# Sheet2.net
KiCad netlist of a schematic drawn in Altium Designer
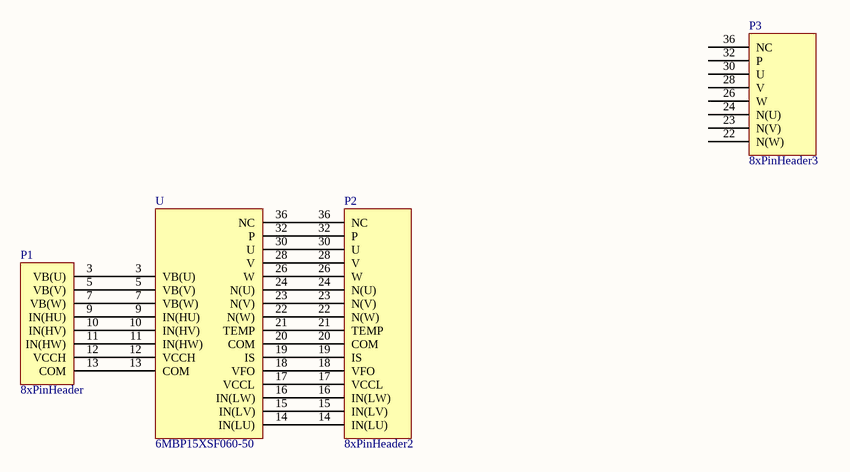
[diagram p0: Sheet2.SchDoc]

(export (version "E")
  (design (tool "Eeschema 10.0.6"))
  (components
    (comp (ref "P1")
      (value "8xPinHeader")
      (footprint "8xPinHeader")
      (libsource (lib "Schlib1") (part "8xPinHeader"))
    )
    (comp (ref "P2")
      (value "8xPinHeader2")
      (footprint "8xPinHeader2")
      (libsource (lib "Schlib1") (part "8xPinHeader2"))
    )
    (comp (ref "P3")
      (value "8xPinHeader3")
      (footprint "8xPinHeader3")
      (libsource (lib "Schlib1") (part "8xPinHeader3"))
    )
    (comp (ref "U")
      (value "6MBP15XSF060-50")
      (footprint "6MBP15XSF060-50")
      (description "600v 15a")
      (libsource (lib "Schlib1") (part "6MBP15XSF060-50"))
    )
  )
  (nets
    (net (code "1") (name "Net-(P1-COM)") (class "Default")
      (node (ref "P1") (pin "13") (pinfunction "COM_13") (pintype "passive"))
      (node (ref "U") (pin "13") (pinfunction "COM_13") (pintype "passive"))
    )
    (net (code "2") (name "Net-(P1-IN(HU))") (class "Default")
      (node (ref "P1") (pin "9") (pinfunction "IN(HU)_9") (pintype "passive"))
      (node (ref "U") (pin "9") (pinfunction "IN(HU)_9") (pintype "passive"))
    )
    (net (code "3") (name "Net-(P1-IN(HV))") (class "Default")
      (node (ref "P1") (pin "10") (pinfunction "IN(HV)_10") (pintype "passive"))
      (node (ref "U") (pin "10") (pinfunction "IN(HV)_10") (pintype "passive"))
    )
    (net (code "4") (name "Net-(P1-IN(HW))") (class "Default")
      (node (ref "P1") (pin "11") (pinfunction "IN(HW)_11") (pintype "passive"))
      (node (ref "U") (pin "11") (pinfunction "IN(HW)_11") (pintype "passive"))
    )
    (net (code "5") (name "Net-(P1-VB(U))") (class "Default")
      (node (ref "P1") (pin "3") (pinfunction "VB(U)_3") (pintype "passive"))
      (node (ref "U") (pin "3") (pinfunction "VB(U)_3") (pintype "passive"))
    )
    (net (code "6") (name "Net-(P1-VB(V))") (class "Default")
      (node (ref "P1") (pin "5") (pinfunction "VB(V)_5") (pintype "passive"))
      (node (ref "U") (pin "5") (pinfunction "VB(V)_5") (pintype "passive"))
    )
    (net (code "7") (name "Net-(P1-VB(W))") (class "Default")
      (node (ref "P1") (pin "7") (pinfunction "VB(W)_7") (pintype "passive"))
      (node (ref "U") (pin "7") (pinfunction "VB(W)_7") (pintype "passive"))
    )
    (net (code "8") (name "Net-(P1-VCCH)") (class "Default")
      (node (ref "P1") (pin "12") (pinfunction "VCCH_12") (pintype "passive"))
      (node (ref "U") (pin "12") (pinfunction "VCCH_12") (pintype "passive"))
    )
    (net (code "9") (name "Net-(P2-COM)") (class "Default")
      (node (ref "P2") (pin "20") (pinfunction "COM_20") (pintype "passive"))
      (node (ref "U") (pin "20") (pinfunction "COM_20") (pintype "passive"))
    )
    (net (code "10") (name "Net-(P2-IN(LU))") (class "Default")
      (node (ref "P2") (pin "14") (pinfunction "IN(LU)_14") (pintype "passive"))
      (node (ref "U") (pin "14") (pinfunction "IN(LU)_14") (pintype "passive"))
    )
    (net (code "11") (name "Net-(P2-IN(LV))") (class "Default")
      (node (ref "P2") (pin "15") (pinfunction "IN(LV)_15") (pintype "passive"))
      (node (ref "U") (pin "15") (pinfunction "IN(LV)_15") (pintype "passive"))
    )
    (net (code "12") (name "Net-(P2-IN(LW))") (class "Default")
      (node (ref "P2") (pin "16") (pinfunction "IN(LW)_16") (pintype "passive"))
      (node (ref "U") (pin "16") (pinfunction "IN(LW)_16") (pintype "passive"))
    )
    (net (code "13") (name "Net-(P2-IS)") (class "Default")
      (node (ref "P2") (pin "19") (pinfunction "IS_19") (pintype "passive"))
      (node (ref "U") (pin "19") (pinfunction "IS_19") (pintype "passive"))
    )
    (net (code "14") (name "Net-(P2-N(U))") (class "Default")
      (node (ref "P2") (pin "24") (pinfunction "N(U)_24") (pintype "passive"))
      (node (ref "U") (pin "24") (pinfunction "N(U)_24") (pintype "passive"))
    )
    (net (code "15") (name "Net-(P2-N(V))") (class "Default")
      (node (ref "P2") (pin "23") (pinfunction "N(V)_23") (pintype "passive"))
      (node (ref "U") (pin "23") (pinfunction "N(V)_23") (pintype "passive"))
    )
    (net (code "16") (name "Net-(P2-N(W))") (class "Default")
      (node (ref "P2") (pin "22") (pinfunction "N(W)_22") (pintype "passive"))
      (node (ref "U") (pin "22") (pinfunction "N(W)_22") (pintype "passive"))
    )
    (net (code "17") (name "Net-(P2-NC)") (class "Default")
      (node (ref "P2") (pin "36") (pinfunction "NC_36") (pintype "passive"))
      (node (ref "U") (pin "36") (pinfunction "NC_36") (pintype "passive"))
    )
    (net (code "18") (name "Net-(P2-P)") (class "Default")
      (node (ref "P2") (pin "32") (pinfunction "P_32") (pintype "passive"))
      (node (ref "U") (pin "32") (pinfunction "P_32") (pintype "passive"))
    )
    (net (code "19") (name "Net-(P2-TEMP)") (class "Default")
      (node (ref "P2") (pin "21") (pinfunction "TEMP_21") (pintype "passive"))
      (node (ref "U") (pin "21") (pinfunction "TEMP_21") (pintype "passive"))
    )
    (net (code "20") (name "Net-(P2-U)") (class "Default")
      (node (ref "P2") (pin "30") (pinfunction "U_30") (pintype "passive"))
      (node (ref "U") (pin "30") (pinfunction "U_30") (pintype "passive"))
    )
    (net (code "21") (name "Net-(P2-V)") (class "Default")
      (node (ref "P2") (pin "28") (pinfunction "V_28") (pintype "passive"))
      (node (ref "U") (pin "28") (pinfunction "V_28") (pintype "passive"))
    )
    (net (code "22") (name "Net-(P2-VCCL)") (class "Default")
      (node (ref "P2") (pin "17") (pinfunction "VCCL_17") (pintype "passive"))
      (node (ref "U") (pin "17") (pinfunction "VCCL_17") (pintype "passive"))
    )
    (net (code "23") (name "Net-(P2-VFO)") (class "Default")
      (node (ref "P2") (pin "18") (pinfunction "VFO_18") (pintype "passive"))
      (node (ref "U") (pin "18") (pinfunction "VFO_18") (pintype "passive"))
    )
    (net (code "24") (name "Net-(P2-W)") (class "Default")
      (node (ref "P2") (pin "26") (pinfunction "W_26") (pintype "passive"))
      (node (ref "U") (pin "26") (pinfunction "W_26") (pintype "passive"))
    )
    (net (code "25") (name "unconnected-(P3-N(U)-Pad24)") (class "Default")
      (node (ref "P3") (pin "24") (pinfunction "N(U)_24") (pintype "passive"))
    )
    (net (code "26") (name "unconnected-(P3-N(V)-Pad23)") (class "Default")
      (node (ref "P3") (pin "23") (pinfunction "N(V)_23") (pintype "passive"))
    )
    (net (code "27") (name "unconnected-(P3-N(W)-Pad22)") (class "Default")
      (node (ref "P3") (pin "22") (pinfunction "N(W)_22") (pintype "passive"))
    )
    (net (code "28") (name "unconnected-(P3-NC-Pad36)") (class "Default")
      (node (ref "P3") (pin "36") (pinfunction "NC_36") (pintype "passive"))
    )
    (net (code "29") (name "unconnected-(P3-P-Pad32)") (class "Default")
      (node (ref "P3") (pin "32") (pinfunction "P_32") (pintype "passive"))
    )
    (net (code "30") (name "unconnected-(P3-U-Pad30)") (class "Default")
      (node (ref "P3") (pin "30") (pinfunction "U_30") (pintype "passive"))
    )
    (net (code "31") (name "unconnected-(P3-V-Pad28)") (class "Default")
      (node (ref "P3") (pin "28") (pinfunction "V_28") (pintype "passive"))
    )
    (net (code "32") (name "unconnected-(P3-W-Pad26)") (class "Default")
      (node (ref "P3") (pin "26") (pinfunction "W_26") (pintype "passive"))
    )
  )
)
